# DriverPNP_Sch.net
KiCad netlist of a schematic drawn in Altium Designer
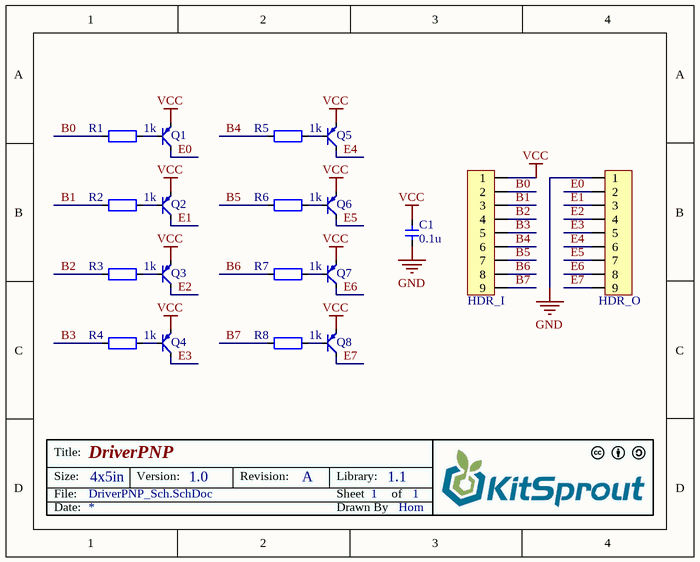
[diagram p0: DriverPNP_Sch.SchDoc]

(export (version "E")
  (design (tool "Eeschema 10.0.6"))
  (components
    (comp (ref "C1")
      (value "0.1u")
      (footprint "PCB_PassiveCap:CAP_0603")
      (description "Capacitor")
      (fields (field (name "Comment") "Cap_0603"))
      (libsource (lib "SCH_Passive") (part "Cap_0603"))
    )
    (comp (ref "HDR_I")
      (value "HDR1x9.54")
      (footprint "PCB_ConnectorHDR:HDR1X9_2.54_180")
      (description "Header")
      (libsource (lib "SCH_ConnectorHDR") (part "HDR1x9_2.54_T"))
    )
    (comp (ref "HDR_O")
      (value "HDR1x9.54")
      (footprint "PCB_ConnectorHDR:HDR1X9_2.54_180")
      (description "Header")
      (libsource (lib "SCH_ConnectorHDR") (part "HDR1x9_2.54"))
    )
    (comp (ref "Q1")
      (value "BJT_PNP")
      (footprint "PCB_IntegratedCircuit:SOT23-3")
      (description "Transistor")
      (libsource (lib "SCH_Active") (part "BJT_PNP"))
    )
    (comp (ref "Q2")
      (value "BJT_PNP")
      (footprint "PCB_IntegratedCircuit:SOT23-3")
      (description "Transistor")
      (libsource (lib "SCH_Active") (part "BJT_PNP"))
    )
    (comp (ref "Q3")
      (value "BJT_PNP")
      (footprint "PCB_IntegratedCircuit:SOT23-3")
      (description "Transistor")
      (libsource (lib "SCH_Active") (part "BJT_PNP"))
    )
    (comp (ref "Q4")
      (value "BJT_PNP")
      (footprint "PCB_IntegratedCircuit:SOT23-3")
      (description "Transistor")
      (libsource (lib "SCH_Active") (part "BJT_PNP"))
    )
    (comp (ref "Q5")
      (value "BJT_PNP")
      (footprint "PCB_IntegratedCircuit:SOT23-3")
      (description "Transistor")
      (libsource (lib "SCH_Active") (part "BJT_PNP"))
    )
    (comp (ref "Q6")
      (value "BJT_PNP")
      (footprint "PCB_IntegratedCircuit:SOT23-3")
      (description "Transistor")
      (libsource (lib "SCH_Active") (part "BJT_PNP"))
    )
    (comp (ref "Q7")
      (value "BJT_PNP")
      (footprint "PCB_IntegratedCircuit:SOT23-3")
      (description "Transistor")
      (libsource (lib "SCH_Active") (part "BJT_PNP"))
    )
    (comp (ref "Q8")
      (value "BJT_PNP")
      (footprint "PCB_IntegratedCircuit:SOT23-3")
      (description "Transistor")
      (libsource (lib "SCH_Active") (part "BJT_PNP"))
    )
    (comp (ref "R1")
      (value "1k")
      (footprint "PCB_PassiveRes:RES_0603")
      (description "Resistor")
      (fields (field (name "Comment") "Res_0603"))
      (libsource (lib "SCH_Passive") (part "Res_0603"))
    )
    (comp (ref "R2")
      (value "1k")
      (footprint "PCB_PassiveRes:RES_0603")
      (description "Resistor")
      (fields (field (name "Comment") "Res_0603"))
      (libsource (lib "SCH_Passive") (part "Res_0603"))
    )
    (comp (ref "R3")
      (value "1k")
      (footprint "PCB_PassiveRes:RES_0603")
      (description "Resistor")
      (fields (field (name "Comment") "Res_0603"))
      (libsource (lib "SCH_Passive") (part "Res_0603"))
    )
    (comp (ref "R4")
      (value "1k")
      (footprint "PCB_PassiveRes:RES_0603")
      (description "Resistor")
      (fields (field (name "Comment") "Res_0603"))
      (libsource (lib "SCH_Passive") (part "Res_0603"))
    )
    (comp (ref "R5")
      (value "1k")
      (footprint "PCB_PassiveRes:RES_0603")
      (description "Resistor")
      (fields (field (name "Comment") "Res_0603"))
      (libsource (lib "SCH_Passive") (part "Res_0603"))
    )
    (comp (ref "R6")
      (value "1k")
      (footprint "PCB_PassiveRes:RES_0603")
      (description "Resistor")
      (fields (field (name "Comment") "Res_0603"))
      (libsource (lib "SCH_Passive") (part "Res_0603"))
    )
    (comp (ref "R7")
      (value "1k")
      (footprint "PCB_PassiveRes:RES_0603")
      (description "Resistor")
      (fields (field (name "Comment") "Res_0603"))
      (libsource (lib "SCH_Passive") (part "Res_0603"))
    )
    (comp (ref "R8")
      (value "1k")
      (footprint "PCB_PassiveRes:RES_0603")
      (description "Resistor")
      (fields (field (name "Comment") "Res_0603"))
      (libsource (lib "SCH_Passive") (part "Res_0603"))
    )
  )
  (nets
    (net (code "1") (name "/B0") (class "Default")
      (node (ref "HDR_I") (pin "2") (pinfunction "2_2") (pintype "passive"))
      (node (ref "R1") (pin "1") (pinfunction "1_1") (pintype "passive"))
    )
    (net (code "2") (name "/B1") (class "Default")
      (node (ref "HDR_I") (pin "3") (pinfunction "3_3") (pintype "passive"))
      (node (ref "R2") (pin "1") (pinfunction "1_1") (pintype "passive"))
    )
    (net (code "3") (name "/B2") (class "Default")
      (node (ref "HDR_I") (pin "4") (pinfunction "4_4") (pintype "passive"))
      (node (ref "R3") (pin "1") (pinfunction "1_1") (pintype "passive"))
    )
    (net (code "4") (name "/B3") (class "Default")
      (node (ref "HDR_I") (pin "5") (pinfunction "5_5") (pintype "passive"))
      (node (ref "R4") (pin "1") (pinfunction "1_1") (pintype "passive"))
    )
    (net (code "5") (name "/B4") (class "Default")
      (node (ref "HDR_I") (pin "6") (pinfunction "6_6") (pintype "passive"))
      (node (ref "R5") (pin "1") (pinfunction "1_1") (pintype "passive"))
    )
    (net (code "6") (name "/B5") (class "Default")
      (node (ref "HDR_I") (pin "7") (pinfunction "7_7") (pintype "passive"))
      (node (ref "R6") (pin "1") (pinfunction "1_1") (pintype "passive"))
    )
    (net (code "7") (name "/B6") (class "Default")
      (node (ref "HDR_I") (pin "8") (pinfunction "8_8") (pintype "passive"))
      (node (ref "R7") (pin "1") (pinfunction "1_1") (pintype "passive"))
    )
    (net (code "8") (name "/B7") (class "Default")
      (node (ref "HDR_I") (pin "9") (pinfunction "9_9") (pintype "passive"))
      (node (ref "R8") (pin "1") (pinfunction "1_1") (pintype "passive"))
    )
    (net (code "9") (name "/E0") (class "Default")
      (node (ref "HDR_O") (pin "2") (pinfunction "2_2") (pintype "passive"))
      (node (ref "Q1") (pin "3") (pinfunction "C_3") (pintype "passive"))
    )
    (net (code "10") (name "/E1") (class "Default")
      (node (ref "HDR_O") (pin "3") (pinfunction "3_3") (pintype "passive"))
      (node (ref "Q2") (pin "3") (pinfunction "C_3") (pintype "passive"))
    )
    (net (code "11") (name "/E2") (class "Default")
      (node (ref "HDR_O") (pin "4") (pinfunction "4_4") (pintype "passive"))
      (node (ref "Q3") (pin "3") (pinfunction "C_3") (pintype "passive"))
    )
    (net (code "12") (name "/E3") (class "Default")
      (node (ref "HDR_O") (pin "5") (pinfunction "5_5") (pintype "passive"))
      (node (ref "Q4") (pin "3") (pinfunction "C_3") (pintype "passive"))
    )
    (net (code "13") (name "/E4") (class "Default")
      (node (ref "HDR_O") (pin "6") (pinfunction "6_6") (pintype "passive"))
      (node (ref "Q5") (pin "3") (pinfunction "C_3") (pintype "passive"))
    )
    (net (code "14") (name "/E5") (class "Default")
      (node (ref "HDR_O") (pin "7") (pinfunction "7_7") (pintype "passive"))
      (node (ref "Q6") (pin "3") (pinfunction "C_3") (pintype "passive"))
    )
    (net (code "15") (name "/E6") (class "Default")
      (node (ref "HDR_O") (pin "8") (pinfunction "8_8") (pintype "passive"))
      (node (ref "Q7") (pin "3") (pinfunction "C_3") (pintype "passive"))
    )
    (net (code "16") (name "/E7") (class "Default")
      (node (ref "HDR_O") (pin "9") (pinfunction "9_9") (pintype "passive"))
      (node (ref "Q8") (pin "3") (pinfunction "C_3") (pintype "passive"))
    )
    (net (code "17") (name "GND") (class "Default")
      (node (ref "C1") (pin "1") (pinfunction "1_1") (pintype "passive"))
      (node (ref "HDR_O") (pin "1") (pinfunction "1_1") (pintype "passive"))
    )
    (net (code "18") (name "Net-(Q1-B)") (class "Default")
      (node (ref "Q1") (pin "1") (pinfunction "B_1") (pintype "passive"))
      (node (ref "R1") (pin "2") (pinfunction "2_2") (pintype "passive"))
    )
    (net (code "19") (name "Net-(Q2-B)") (class "Default")
      (node (ref "Q2") (pin "1") (pinfunction "B_1") (pintype "passive"))
      (node (ref "R2") (pin "2") (pinfunction "2_2") (pintype "passive"))
    )
    (net (code "20") (name "Net-(Q3-B)") (class "Default")
      (node (ref "Q3") (pin "1") (pinfunction "B_1") (pintype "passive"))
      (node (ref "R3") (pin "2") (pinfunction "2_2") (pintype "passive"))
    )
    (net (code "21") (name "Net-(Q4-B)") (class "Default")
      (node (ref "Q4") (pin "1") (pinfunction "B_1") (pintype "passive"))
      (node (ref "R4") (pin "2") (pinfunction "2_2") (pintype "passive"))
    )
    (net (code "22") (name "Net-(Q5-B)") (class "Default")
      (node (ref "Q5") (pin "1") (pinfunction "B_1") (pintype "passive"))
      (node (ref "R5") (pin "2") (pinfunction "2_2") (pintype "passive"))
    )
    (net (code "23") (name "Net-(Q6-B)") (class "Default")
      (node (ref "Q6") (pin "1") (pinfunction "B_1") (pintype "passive"))
      (node (ref "R6") (pin "2") (pinfunction "2_2") (pintype "passive"))
    )
    (net (code "24") (name "Net-(Q7-B)") (class "Default")
      (node (ref "Q7") (pin "1") (pinfunction "B_1") (pintype "passive"))
      (node (ref "R7") (pin "2") (pinfunction "2_2") (pintype "passive"))
    )
    (net (code "25") (name "Net-(Q8-B)") (class "Default")
      (node (ref "Q8") (pin "1") (pinfunction "B_1") (pintype "passive"))
      (node (ref "R8") (pin "2") (pinfunction "2_2") (pintype "passive"))
    )
    (net (code "26") (name "VCC") (class "Default")
      (node (ref "C1") (pin "2") (pinfunction "2_2") (pintype "passive"))
      (node (ref "HDR_I") (pin "1") (pinfunction "1_1") (pintype "passive"))
      (node (ref "Q1") (pin "2") (pinfunction "E_2") (pintype "passive"))
      (node (ref "Q2") (pin "2") (pinfunction "E_2") (pintype "passive"))
      (node (ref "Q3") (pin "2") (pinfunction "E_2") (pintype "passive"))
      (node (ref "Q4") (pin "2") (pinfunction "E_2") (pintype "passive"))
      (node (ref "Q5") (pin "2") (pinfunction "E_2") (pintype "passive"))
      (node (ref "Q6") (pin "2") (pinfunction "E_2") (pintype "passive"))
      (node (ref "Q7") (pin "2") (pinfunction "E_2") (pintype "passive"))
      (node (ref "Q8") (pin "2") (pinfunction "E_2") (pintype "passive"))
    )
  )
)
